# Sheet1.net
KiCad netlist of a schematic drawn in Altium Designer
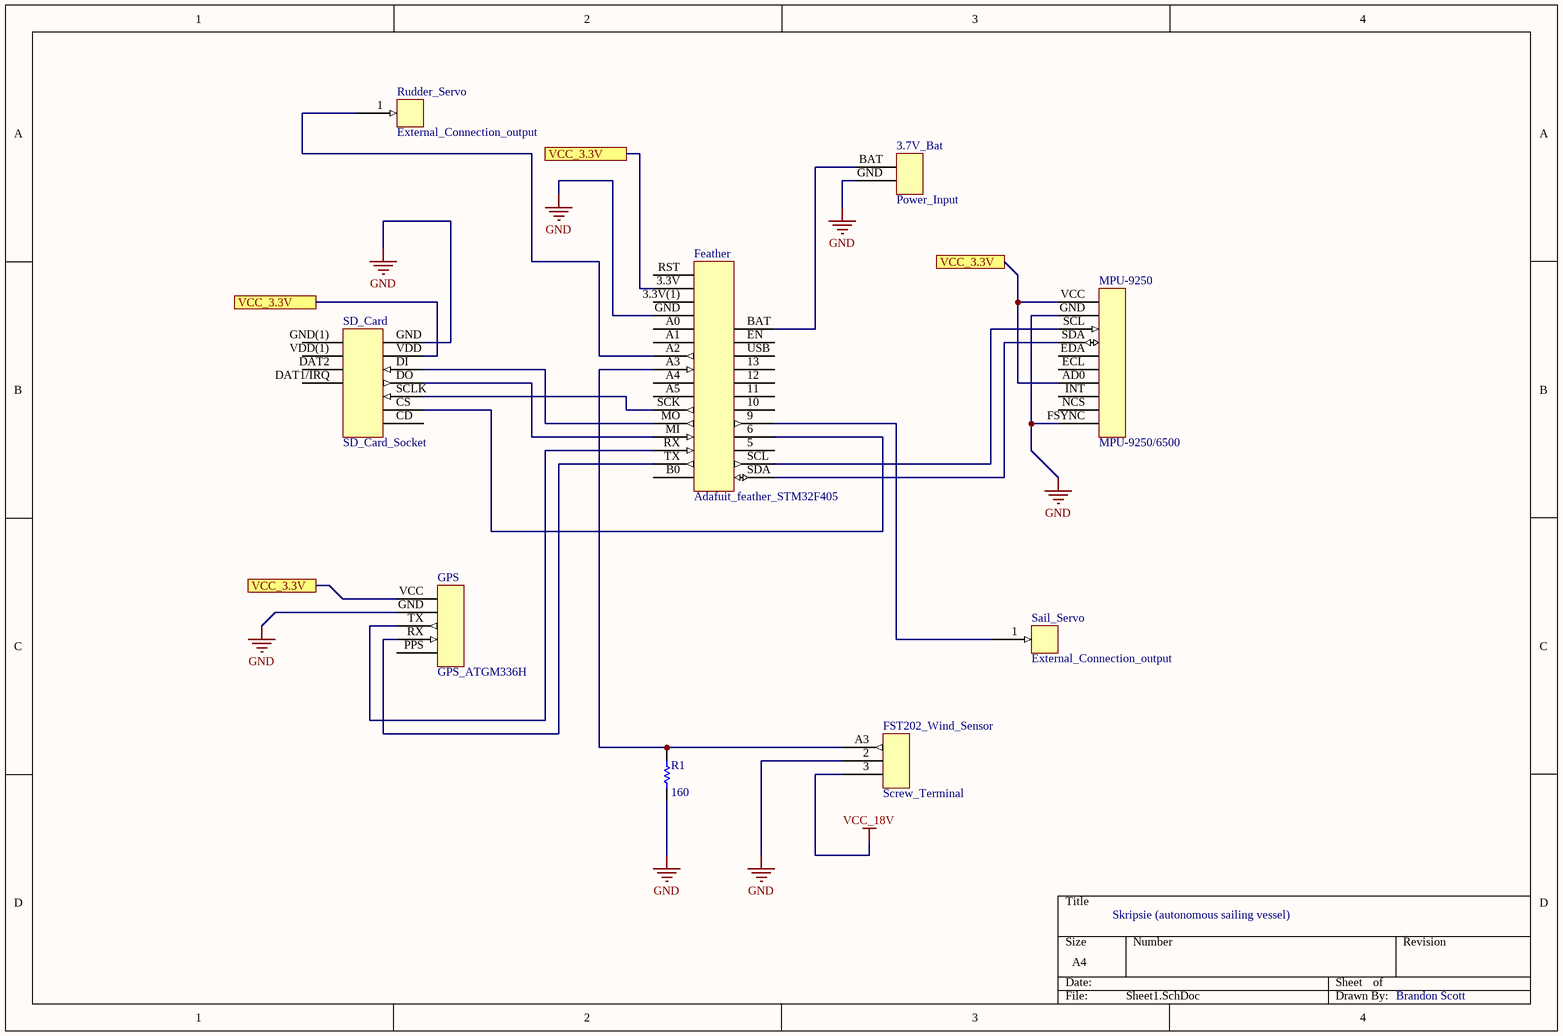
[diagram p0: Sheet1.SchDoc]

(export (version "E")
  (design (tool "Eeschema 10.0.6"))
  (components
    (comp (ref "3.7V_Bat")
      (value "Power_Input")
      (footprint "Power_Input")
      (libsource (lib "Schlib1") (part "Power_Input"))
    )
    (comp (ref "Feather")
      (value "Adafuit_feather_STM32F405")
      (footprint "Adafuit_feather_STM32F405")
      (libsource (lib "Schlib1") (part "Adafuit_feather_STM32F405"))
    )
    (comp (ref "FST202_Wind_Sensor")
      (value "Screw_Terminal")
      (footprint "Screw_Terminal")
      (libsource (lib "Schlib1") (part "Screw_Terminal"))
    )
    (comp (ref "GPS")
      (value "GPS_ATGM336H")
      (footprint "GPS")
      (libsource (lib "Schlib1") (part "GPS_ATGM336H"))
    )
    (comp (ref "MPU-9250")
      (value "MPU-9250/6500")
      (footprint "MPU-9250/6500")
      (libsource (lib "Schlib1") (part "MPU-9250/6500"))
    )
    (comp (ref "R1")
      (value "160")
      (footprint "Resistor")
      (description "Resistor")
      (fields (field (name "Comment") "Res1") (field (name "PUBLISHER") "Altium Limited"))
      (libsource (lib "Miscellaneous Devices") (part "Res1"))
    )
    (comp (ref "Rudder_Servo")
      (value "External_Connection_output")
      (footprint "connector")
      (libsource (lib "Schlib1") (part "External_Connection_output"))
    )
    (comp (ref "Sail_Servo")
      (value "External_Connection_output")
      (footprint "connector")
      (libsource (lib "Schlib1") (part "External_Connection_output"))
    )
    (comp (ref "SD_Card")
      (value "SD_Card_Socket")
      (footprint "SD_Card_Socket")
      (libsource (lib "Schlib1") (part "SD_Card_Socket"))
    )
  )
  (nets
    (net (code "1") (name "/VCC_3.3V") (class "Default")
      (node (ref "Feather") (pin "3.3V") (pintype "power_in"))
      (node (ref "GPS") (pin "VCC") (pintype "power_in"))
      (node (ref "MPU-9250") (pin "AD0") (pintype "power_in"))
      (node (ref "MPU-9250") (pin "VCC") (pintype "power_in"))
      (node (ref "SD_Card") (pin "VDD") (pintype "power_in"))
    )
    (net (code "2") (name "GND") (class "Default")
      (node (ref "3.7V_Bat") (pin "GND") (pintype "power_in"))
      (node (ref "FST202_Wind_Sensor") (pin "2") (pintype "passive"))
      (node (ref "Feather") (pin "GND") (pintype "power_in"))
      (node (ref "GPS") (pin "GND") (pintype "power_in"))
      (node (ref "MPU-9250") (pin "FSYNC") (pintype "power_in"))
      (node (ref "MPU-9250") (pin "GND") (pintype "power_in"))
      (node (ref "R1") (pin "2") (pinfunction "2_2") (pintype "passive"))
      (node (ref "SD_Card") (pin "GND") (pintype "power_in"))
    )
    (net (code "3") (name "Net-(3.7V_Bat-PadBAT)") (class "Default")
      (node (ref "3.7V_Bat") (pin "BAT") (pintype "power_in"))
      (node (ref "Feather") (pin "BAT") (pintype "power_in"))
    )
    (net (code "4") (name "Net-(FST202_Wind_Sensor-PadA3)") (class "Default")
      (node (ref "FST202_Wind_Sensor") (pin "A3") (pintype "output"))
      (node (ref "Feather") (pin "A3") (pintype "input"))
      (node (ref "R1") (pin "1") (pinfunction "1_1") (pintype "passive"))
    )
    (net (code "5") (name "Net-(Feather-Pad6)") (class "Default")
      (node (ref "Feather") (pin "6") (pintype "passive"))
      (node (ref "SD_Card") (pin "CS") (pintype "passive"))
    )
    (net (code "6") (name "Net-(Feather-Pad9)") (class "Default")
      (node (ref "Feather") (pin "9") (pintype "output"))
      (node (ref "Sail_Servo") (pin "1") (pintype "input"))
    )
    (net (code "7") (name "Net-(Feather-PadA2)") (class "Default")
      (node (ref "Feather") (pin "A2") (pintype "output"))
      (node (ref "Rudder_Servo") (pin "1") (pintype "input"))
    )
    (net (code "8") (name "Net-(Feather-PadMI)") (class "Default")
      (node (ref "Feather") (pin "MI") (pintype "input"))
      (node (ref "SD_Card") (pin "DO") (pintype "output"))
    )
    (net (code "9") (name "Net-(Feather-PadMO)") (class "Default")
      (node (ref "Feather") (pin "MO") (pintype "output"))
      (node (ref "SD_Card") (pin "DI") (pintype "input"))
    )
    (net (code "10") (name "Net-(Feather-PadRX)") (class "Default")
      (node (ref "Feather") (pin "RX") (pintype "input"))
      (node (ref "GPS") (pin "TX") (pintype "output"))
    )
    (net (code "11") (name "Net-(Feather-PadSCK)") (class "Default")
      (node (ref "Feather") (pin "SCK") (pintype "output"))
      (node (ref "SD_Card") (pin "SCLK") (pintype "input"))
    )
    (net (code "12") (name "Net-(Feather-PadSCL)") (class "Default")
      (node (ref "Feather") (pin "SCL") (pintype "output"))
      (node (ref "MPU-9250") (pin "SCL") (pintype "input"))
    )
    (net (code "13") (name "Net-(Feather-PadSDA)") (class "Default")
      (node (ref "Feather") (pin "SDA") (pintype "bidirectional"))
      (node (ref "MPU-9250") (pin "SDA") (pintype "bidirectional"))
    )
    (net (code "14") (name "Net-(Feather-PadTX)") (class "Default")
      (node (ref "Feather") (pin "TX") (pintype "output"))
      (node (ref "GPS") (pin "RX") (pintype "input"))
    )
    (net (code "15") (name "VCC_18V") (class "Default")
      (node (ref "FST202_Wind_Sensor") (pin "3") (pintype "power_in"))
    )
    (net (code "16") (name "unconnected-(Feather-Pad3.3V(1))") (class "Default")
      (node (ref "Feather") (pin "3.3V(1)") (pintype "passive"))
    )
    (net (code "17") (name "unconnected-(Feather-Pad5)") (class "Default")
      (node (ref "Feather") (pin "5") (pintype "passive"))
    )
    (net (code "18") (name "unconnected-(Feather-Pad10)") (class "Default")
      (node (ref "Feather") (pin "10") (pintype "passive"))
    )
    (net (code "19") (name "unconnected-(Feather-Pad11)") (class "Default")
      (node (ref "Feather") (pin "11") (pintype "passive"))
    )
    (net (code "20") (name "unconnected-(Feather-Pad12)") (class "Default")
      (node (ref "Feather") (pin "12") (pintype "passive"))
    )
    (net (code "21") (name "unconnected-(Feather-Pad13)") (class "Default")
      (node (ref "Feather") (pin "13") (pintype "passive"))
    )
    (net (code "22") (name "unconnected-(Feather-PadA0)") (class "Default")
      (node (ref "Feather") (pin "A0") (pintype "passive"))
    )
    (net (code "23") (name "unconnected-(Feather-PadA1)") (class "Default")
      (node (ref "Feather") (pin "A1") (pintype "passive"))
    )
    (net (code "24") (name "unconnected-(Feather-PadA4)") (class "Default")
      (node (ref "Feather") (pin "A4") (pintype "passive"))
    )
    (net (code "25") (name "unconnected-(Feather-PadA5)") (class "Default")
      (node (ref "Feather") (pin "A5") (pintype "passive"))
    )
    (net (code "26") (name "unconnected-(Feather-PadB0)") (class "Default")
      (node (ref "Feather") (pin "B0") (pintype "passive"))
    )
    (net (code "27") (name "unconnected-(Feather-PadEN)") (class "Default")
      (node (ref "Feather") (pin "EN") (pintype "passive"))
    )
    (net (code "28") (name "unconnected-(Feather-PadRST)") (class "Default")
      (node (ref "Feather") (pin "RST") (pintype "passive"))
    )
    (net (code "29") (name "unconnected-(Feather-PadUSB)") (class "Default")
      (node (ref "Feather") (pin "USB") (pintype "passive"))
    )
    (net (code "30") (name "unconnected-(GPS-PadPPS)") (class "Default")
      (node (ref "GPS") (pin "PPS") (pintype "passive"))
    )
    (net (code "31") (name "unconnected-(MPU-9250-PadECL)") (class "Default")
      (node (ref "MPU-9250") (pin "ECL") (pintype "passive"))
    )
    (net (code "32") (name "unconnected-(MPU-9250-PadEDA)") (class "Default")
      (node (ref "MPU-9250") (pin "EDA") (pintype "passive"))
    )
    (net (code "33") (name "unconnected-(MPU-9250-PadINT)") (class "Default")
      (node (ref "MPU-9250") (pin "INT") (pintype "passive"))
    )
    (net (code "34") (name "unconnected-(MPU-9250-PadNCS)") (class "Default")
      (node (ref "MPU-9250") (pin "NCS") (pintype "passive"))
    )
    (net (code "35") (name "unconnected-(SD_Card-PadCD)") (class "Default")
      (node (ref "SD_Card") (pin "CD") (pintype "passive"))
    )
    (net (code "36") (name "unconnected-(SD_Card-PadDAT1{slash}IRQ)") (class "Default")
      (node (ref "SD_Card") (pin "DAT1/IRQ") (pintype "passive"))
    )
    (net (code "37") (name "unconnected-(SD_Card-PadDAT2)") (class "Default")
      (node (ref "SD_Card") (pin "DAT2") (pintype "passive"))
    )
    (net (code "38") (name "unconnected-(SD_Card-PadGND(1))") (class "Default")
      (node (ref "SD_Card") (pin "GND(1)") (pintype "passive"))
    )
    (net (code "39") (name "unconnected-(SD_Card-PadVDD(1))") (class "Default")
      (node (ref "SD_Card") (pin "VDD(1)") (pintype "passive"))
    )
  )
)
